# 2_Microcontroler_48.net
KiCad netlist of a schematic drawn in Altium Designer
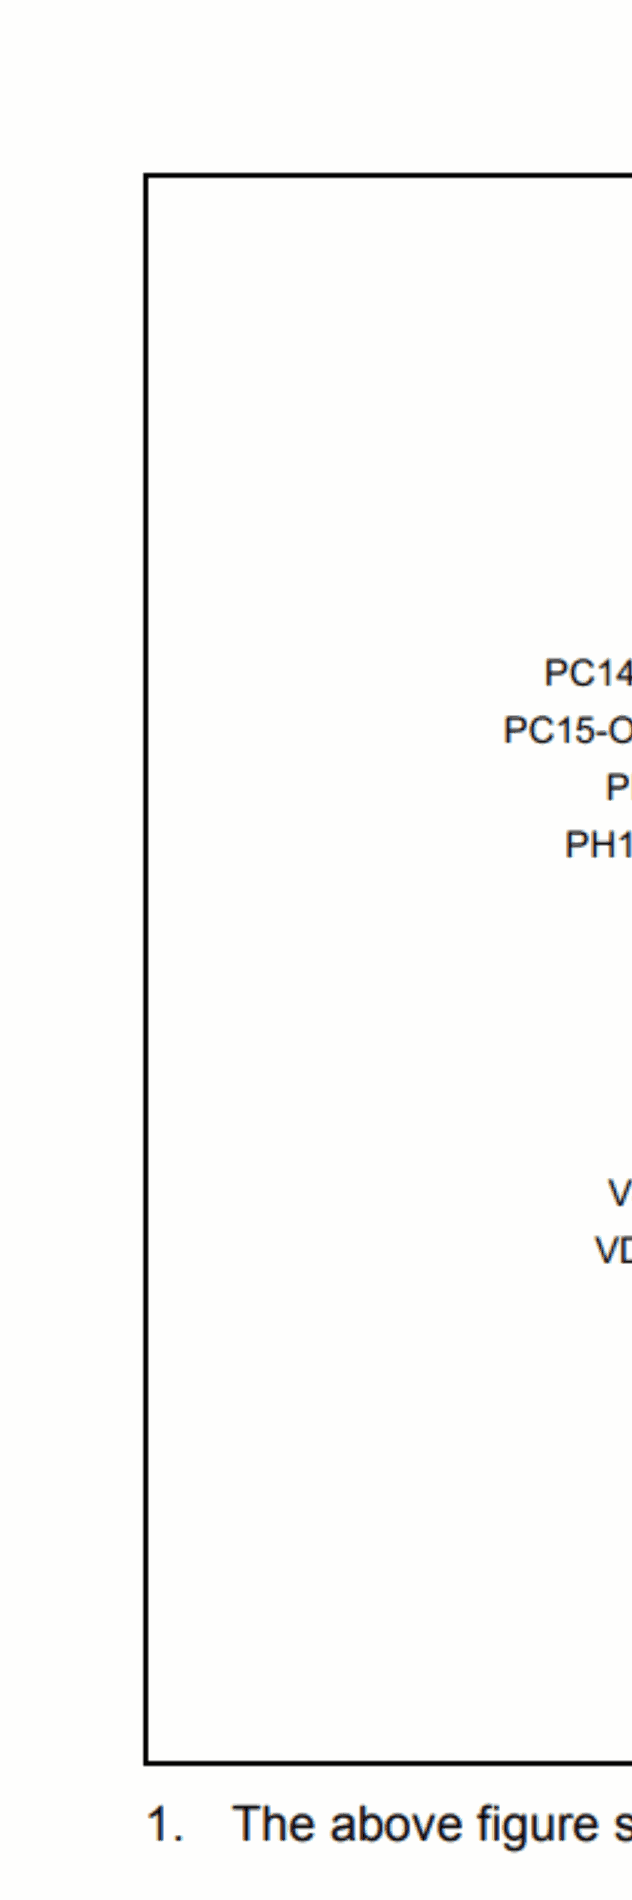
[diagram p0: 2_Microcontroler_48.SchDoc, top left]
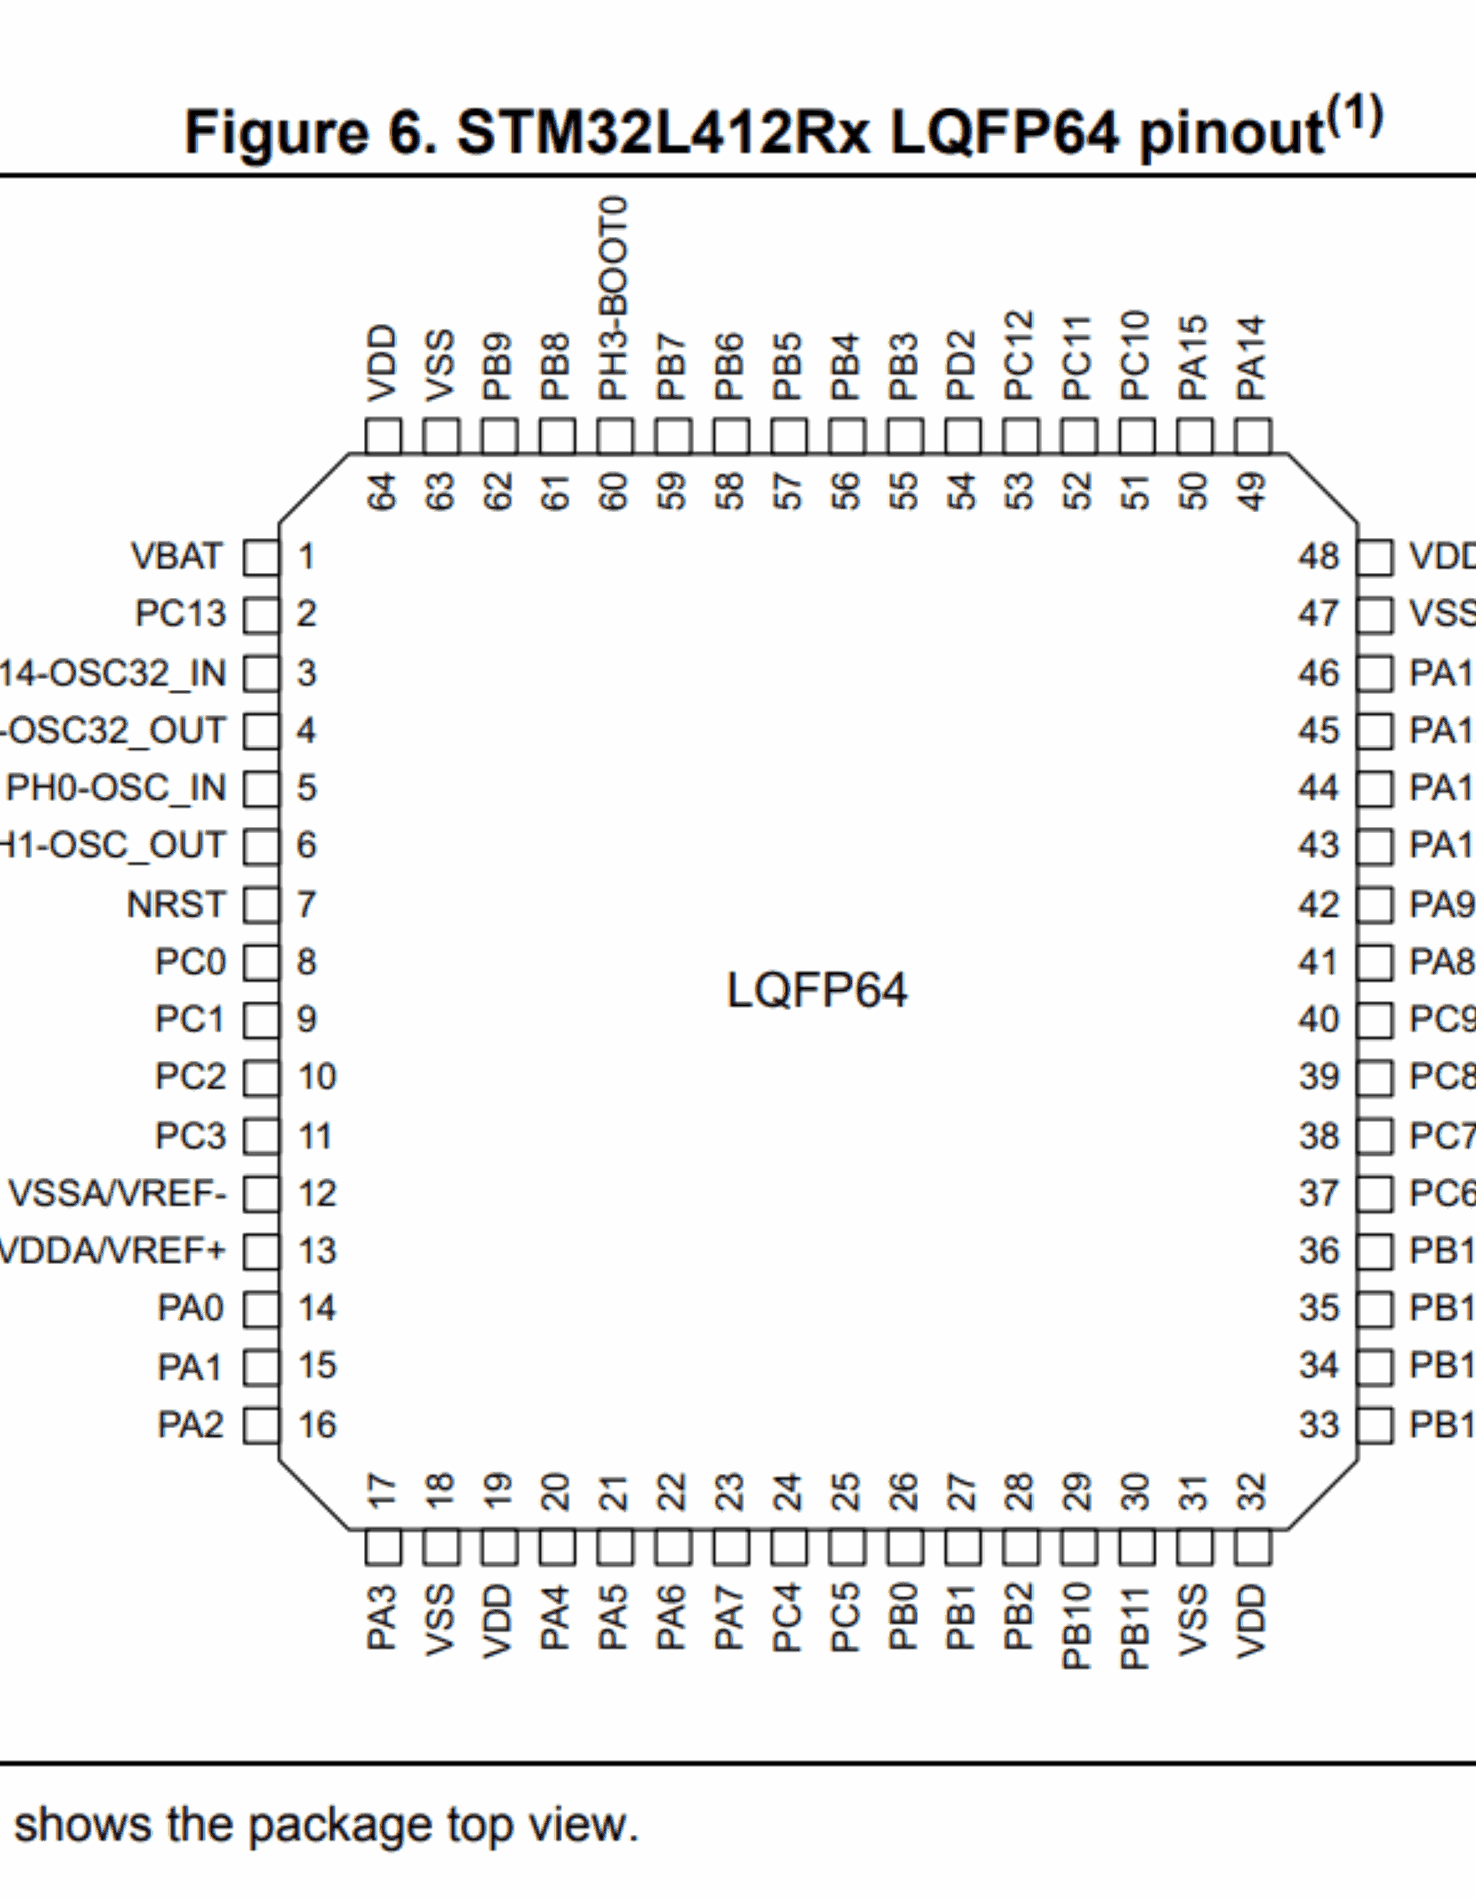
[diagram p1: 2_Microcontroler_48.SchDoc, top middle]
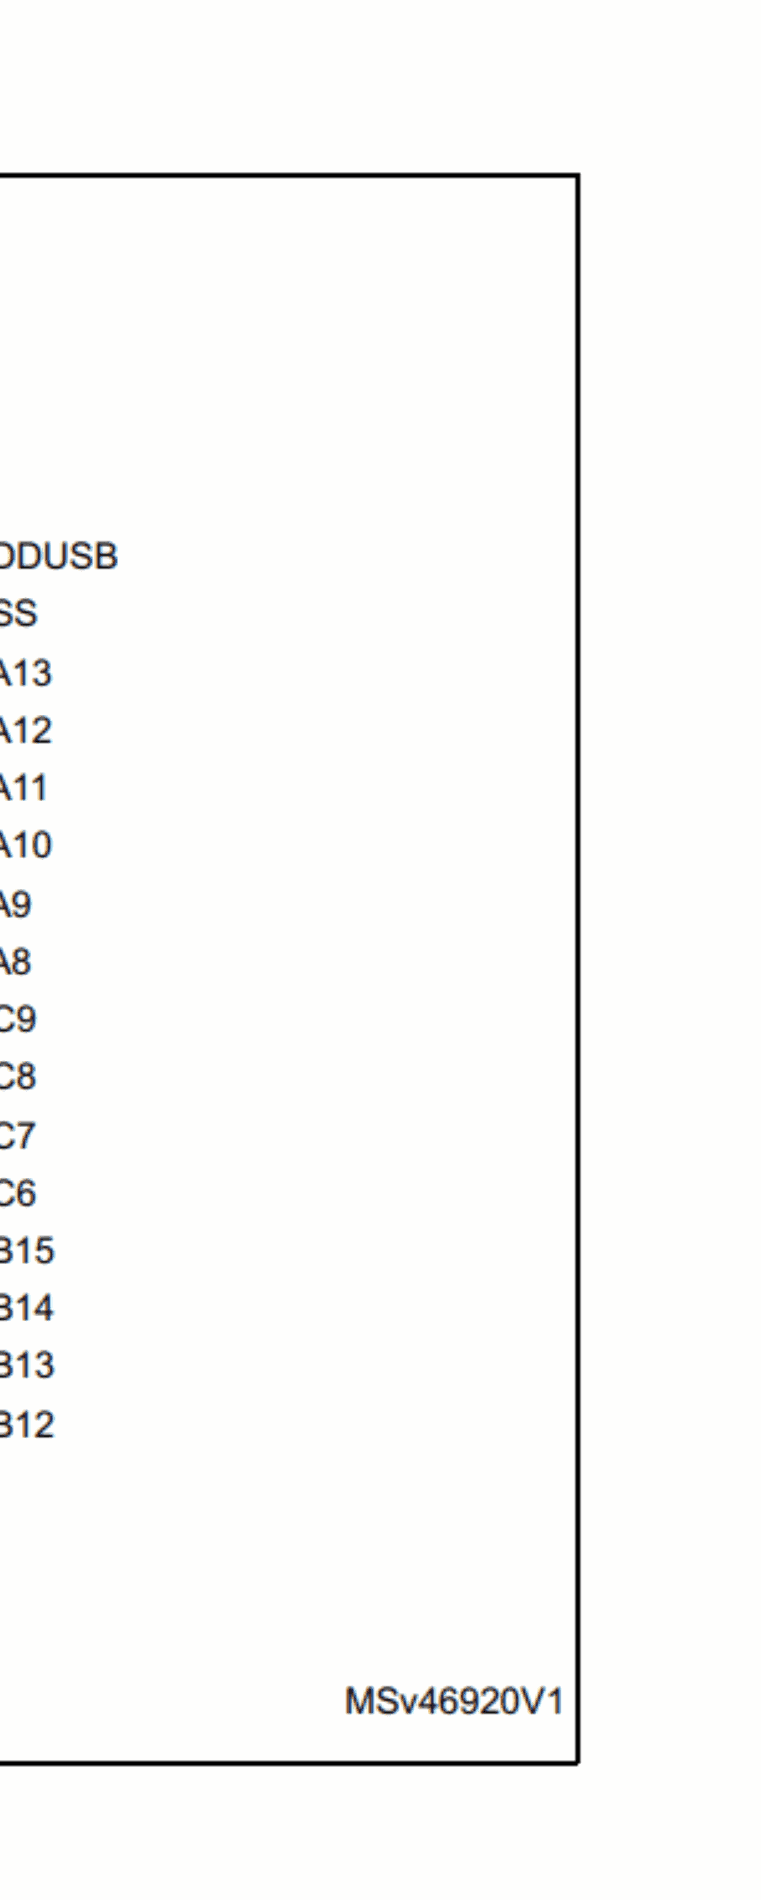
[diagram p2: 2_Microcontroler_48.SchDoc, top right]
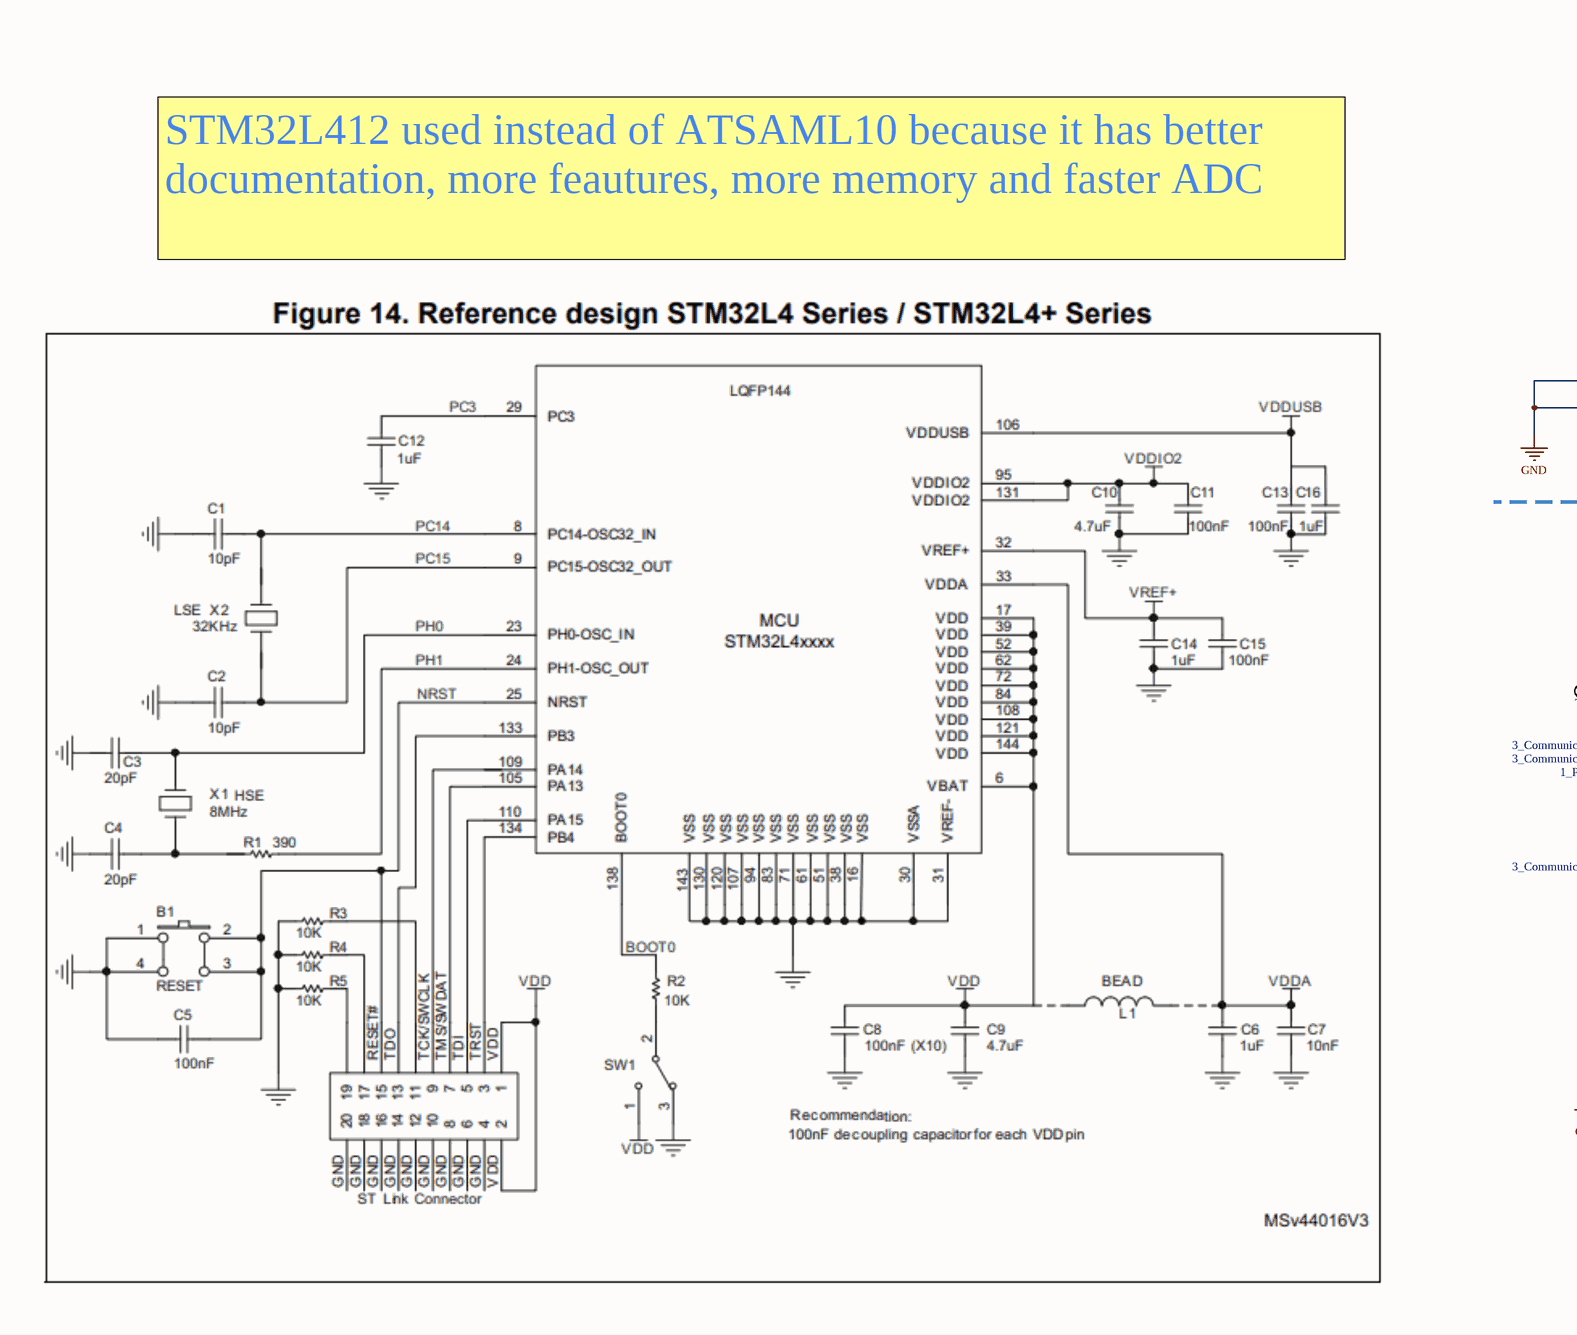
[diagram p3: 2_Microcontroler_48.SchDoc, bottom left]
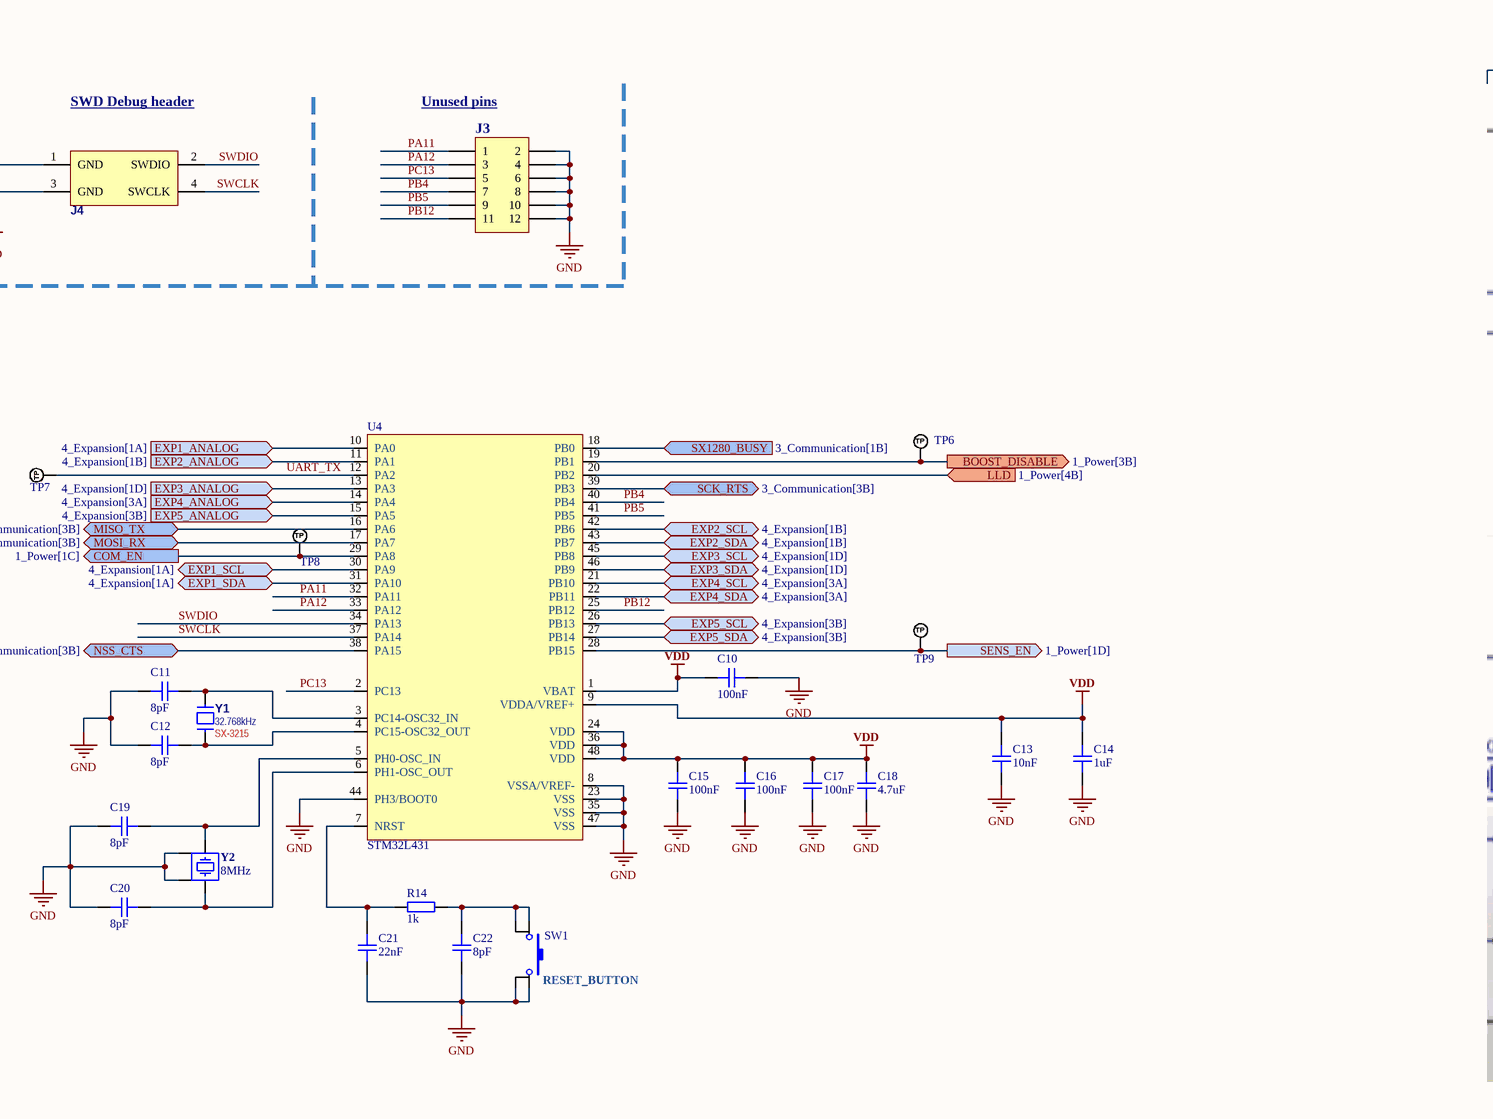
[diagram p4: 2_Microcontroler_48.SchDoc, bottom middle]
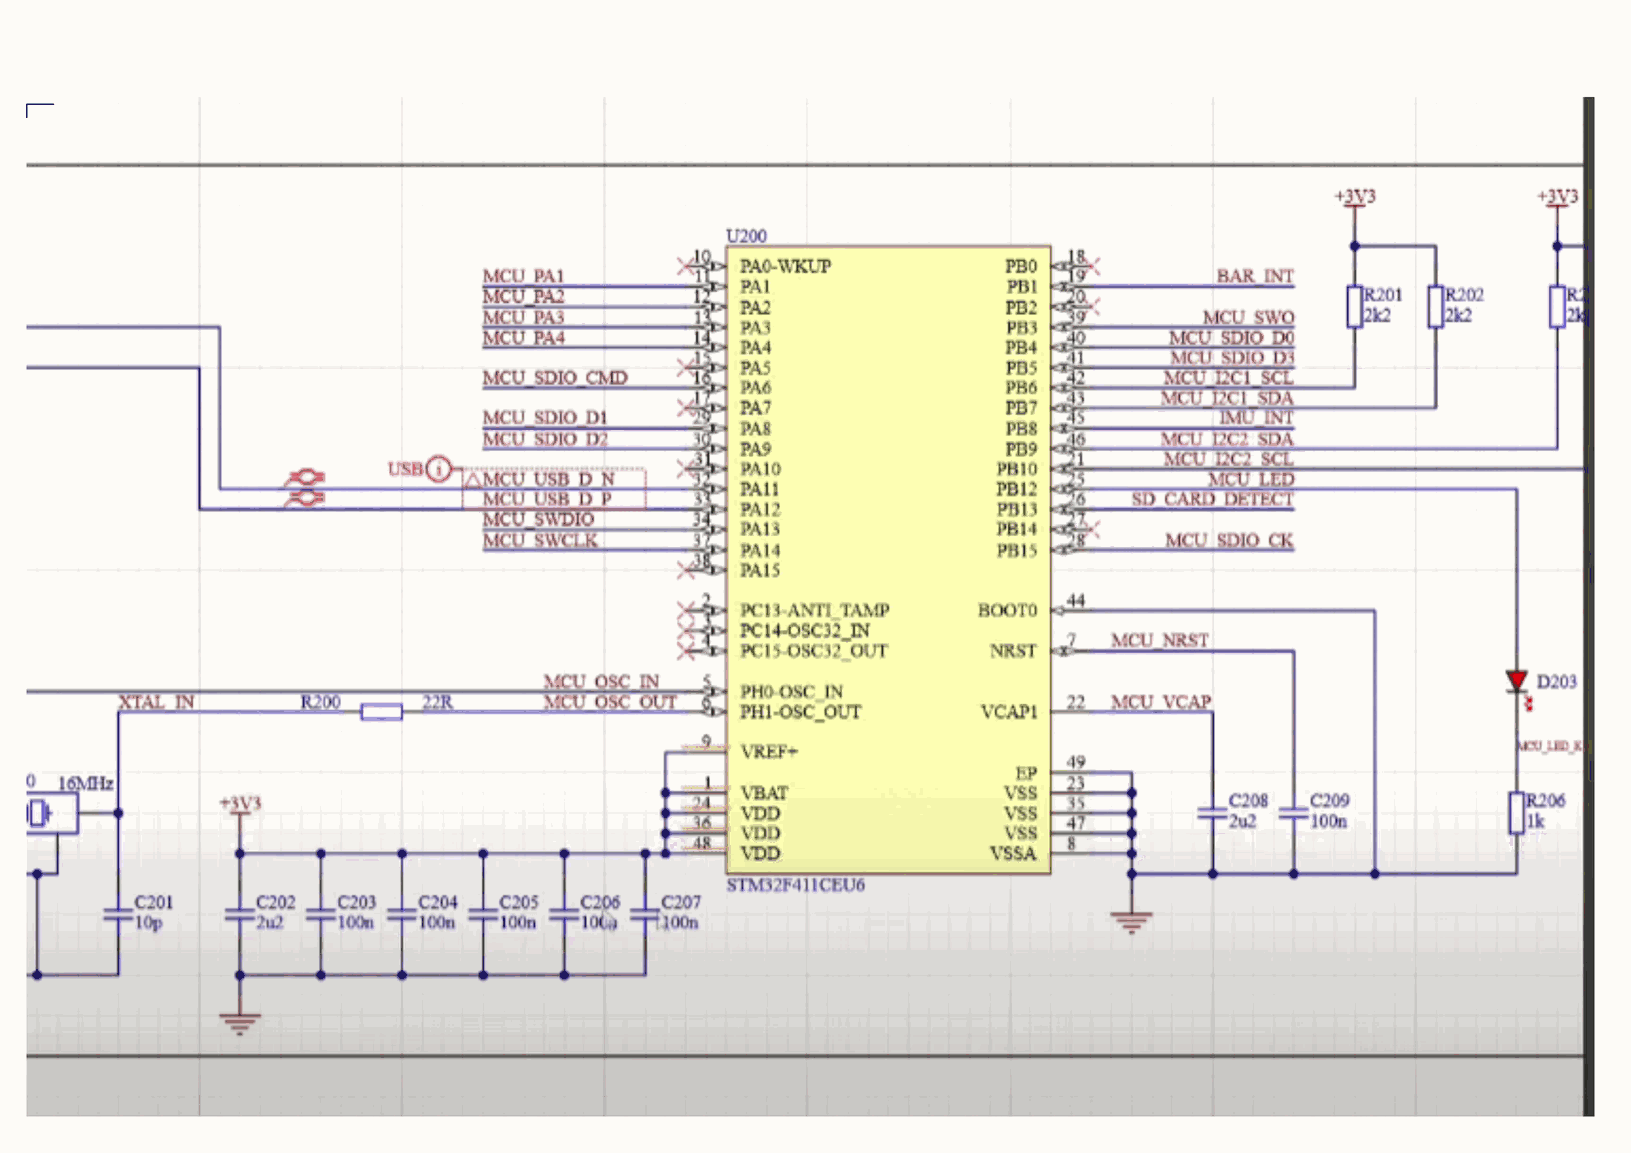
[diagram p5: 2_Microcontroler_48.SchDoc, bottom right]

(export (version "E")
  (design (tool "Eeschema 10.0.6"))
  (components
    (comp (ref "C10")
      (value "100nF")
      (footprint "C0603")
      (description "Capacitor SMD 0603")
      (libsource (lib "Schlib_H2") (part "CAP_0603"))
    )
    (comp (ref "C11")
      (value "8pF")
      (footprint "C0603")
      (description "Capacitor SMD 0603")
      (libsource (lib "Schlib_H2") (part "CAP_0603"))
    )
    (comp (ref "C12")
      (value "8pF")
      (footprint "C0603")
      (description "Capacitor SMD 0603")
      (libsource (lib "Schlib_H2") (part "CAP_0603"))
    )
    (comp (ref "C13")
      (value "10nF")
      (footprint "C0603")
      (description "Capacitor SMD 0603")
      (libsource (lib "Schlib_H2") (part "CAP_0603"))
    )
    (comp (ref "C14")
      (value "1uF")
      (footprint "C0603")
      (description "Capacitor SMD 0603")
      (libsource (lib "Schlib_H2") (part "CAP_0603"))
    )
    (comp (ref "C15")
      (value "100nF")
      (footprint "C0603")
      (description "Capacitor SMD 0603")
      (libsource (lib "Schlib_H2") (part "CAP_0603"))
    )
    (comp (ref "C16")
      (value "100nF")
      (footprint "C0603")
      (description "Capacitor SMD 0603")
      (libsource (lib "Schlib_H2") (part "CAP_0603"))
    )
    (comp (ref "C17")
      (value "100nF")
      (footprint "C0603")
      (description "Capacitor SMD 0603")
      (libsource (lib "Schlib_H2") (part "CAP_0603"))
    )
    (comp (ref "C18")
      (value "4.7uF")
      (footprint "C0603")
      (description "Capacitor SMD 0603")
      (libsource (lib "Schlib_H2") (part "CAP_0603"))
    )
    (comp (ref "C19")
      (value "8pF")
      (footprint "C0603")
      (description "Capacitor SMD 0603")
      (libsource (lib "Schlib_H2") (part "CAP_0603"))
    )
    (comp (ref "C20")
      (value "8pF")
      (footprint "C0603")
      (description "Capacitor SMD 0603")
      (libsource (lib "Schlib_H2") (part "CAP_0603"))
    )
    (comp (ref "C21")
      (value "22nF")
      (footprint "C0603")
      (description "Capacitor SMD 0603")
      (libsource (lib "Schlib_H2") (part "CAP_0603"))
    )
    (comp (ref "C22")
      (value "8pF")
      (footprint "C0603")
      (description "Capacitor SMD 0603")
      (libsource (lib "Schlib_H2") (part "CAP_0603"))
    )
    (comp (ref "J3")
      (value "Header 6X2")
      (footprint "HEADER_6x2_2.54")
      (description "Header, 12-Pin, Dual row")
      (fields (field (name "PUBLISHER") "Altium Limited"))
      (libsource (lib "Schlib_H2") (part "Header 6x2"))
    )
    (comp (ref "J4")
      (value "SWD connector")
      (footprint "HEADER_2x2_2.54")
      (description "Single Wire Debug connector with UART _TX pin")
      (libsource (lib "Schlib_H2") (part "SWD connector"))
    )
    (comp (ref "R14")
      (value "1k")
      (footprint "R0603")
      (description "Resistor SMD 0603")
      (libsource (lib "Schlib_H2") (part "RES_0603"))
    )
    (comp (ref "SW1")
      (value "PTS645SM43SMTR92 LFS")
      (footprint "SW_SKRPACE010")
      (description "Switch")
      (fields (field (name "PUBLISHER") "Altium Limited"))
      (libsource (lib "Schlib_H2") (part "SW-PB"))
    )
    (comp (ref "TP6")
      (value "TP_NOBOM")
      (footprint "TEST_PAD_THD")
      (description "Test Point Round 1mm (NO BOM)")
      (libsource (lib "Schlib_H2") (part "TEST_POINT_RND_1MM"))
    )
    (comp (ref "TP7")
      (value "TP_NOBOM")
      (footprint "TEST_PAD_THD")
      (description "Test Point Round 1mm (NO BOM)")
      (libsource (lib "Schlib_H2") (part "TEST_POINT_RND_1MM"))
    )
    (comp (ref "TP8")
      (value "TP_NOBOM")
      (footprint "TEST_PAD_THD")
      (description "Test Point Round 1mm (NO BOM)")
      (libsource (lib "Schlib_H2") (part "TEST_POINT_RND_1MM"))
    )
    (comp (ref "TP9")
      (value "TP_NOBOM")
      (footprint "TEST_PAD_THD")
      (description "Test Point Round 1mm (NO BOM)")
      (libsource (lib "Schlib_H2") (part "TEST_POINT_RND_1MM"))
    )
    (comp (ref "U4")
      (value "STM32L431")
      (footprint "QFPN-48")
      (description "Ultra-low-power Arm® Cortex®-M4 32-bit MCU+FPU, 100DMIPS,\r\n up to 128KB flash, 40KB SRAM(LQFP48)")
      (libsource (lib "Schlib_H2") (part "STM32L431"))
    )
    (comp (ref "Y1")
      (value "32.768kHz")
      (footprint "CRYSTAL_SX-3215")
      (description "Crystal")
      (fields (field (name "PACKAGEREFERENCE") "SX-3215"))
      (libsource (lib "Schlib_H2") (part "CRYSTAL_1"))
    )
    (comp (ref "Y2")
      (value "8MHz")
      (footprint "CRYSTAL_ECX-32_3.2x2.5x0.8 - duplicate")
      (description "Crystal")
      (fields
        (field (name "MANUFACTURER") "Epson")
        (field (name "MANUFACTURER PART NUMBER") "TSX-3225 24.0000MF15X-AC")
      )
      (libsource (lib "Schlib_H2") (part "Crystal"))
    )
  )
  (nets
    (net (code "1") (name "/BOOST_DISABLE") (class "Default")
      (node (ref "TP6") (pin "1") (pinfunction "TP_1") (pintype "passive"))
      (node (ref "U4") (pin "19") (pinfunction "PB1_19") (pintype "passive"))
    )
    (net (code "2") (name "/COM_EN") (class "Default")
      (node (ref "TP8") (pin "1") (pinfunction "TP_1") (pintype "passive"))
      (node (ref "U4") (pin "29") (pinfunction "PA8_29") (pintype "passive"))
    )
    (net (code "3") (name "/EXP1_ANALOG") (class "Default")
      (node (ref "U4") (pin "10") (pinfunction "PA0_10") (pintype "passive"))
    )
    (net (code "4") (name "/EXP1_SCL") (class "Default")
      (node (ref "U4") (pin "30") (pinfunction "PA9_30") (pintype "passive"))
    )
    (net (code "5") (name "/EXP1_SDA") (class "Default")
      (node (ref "U4") (pin "31") (pinfunction "PA10_31") (pintype "passive"))
    )
    (net (code "6") (name "/EXP2_ANALOG") (class "Default")
      (node (ref "U4") (pin "11") (pinfunction "PA1_11") (pintype "passive"))
    )
    (net (code "7") (name "/EXP2_SCL") (class "Default")
      (node (ref "U4") (pin "42") (pinfunction "PB6_42") (pintype "passive"))
    )
    (net (code "8") (name "/EXP2_SDA") (class "Default")
      (node (ref "U4") (pin "43") (pinfunction "PB7_43") (pintype "passive"))
    )
    (net (code "9") (name "/EXP3_ANALOG") (class "Default")
      (node (ref "U4") (pin "13") (pinfunction "PA3_13") (pintype "passive"))
    )
    (net (code "10") (name "/EXP3_SCL") (class "Default")
      (node (ref "U4") (pin "45") (pinfunction "PB8_45") (pintype "passive"))
    )
    (net (code "11") (name "/EXP3_SDA") (class "Default")
      (node (ref "U4") (pin "46") (pinfunction "PB9_46") (pintype "passive"))
    )
    (net (code "12") (name "/EXP4_ANALOG") (class "Default")
      (node (ref "U4") (pin "14") (pinfunction "PA4_14") (pintype "passive"))
    )
    (net (code "13") (name "/EXP4_SCL") (class "Default")
      (node (ref "U4") (pin "21") (pinfunction "PB10_21") (pintype "passive"))
    )
    (net (code "14") (name "/EXP4_SDA") (class "Default")
      (node (ref "U4") (pin "22") (pinfunction "PB11_22") (pintype "passive"))
    )
    (net (code "15") (name "/EXP5_ANALOG") (class "Default")
      (node (ref "U4") (pin "15") (pinfunction "PA5_15") (pintype "passive"))
    )
    (net (code "16") (name "/EXP5_SCL") (class "Default")
      (node (ref "U4") (pin "26") (pinfunction "PB13_26") (pintype "passive"))
    )
    (net (code "17") (name "/EXP5_SDA") (class "Default")
      (node (ref "U4") (pin "27") (pinfunction "PB14_27") (pintype "passive"))
    )
    (net (code "18") (name "/LLD") (class "Default")
      (node (ref "U4") (pin "20") (pinfunction "PB2_20") (pintype "passive"))
    )
    (net (code "19") (name "/MISO_TX") (class "Default")
      (node (ref "U4") (pin "16") (pinfunction "PA6_16") (pintype "passive"))
    )
    (net (code "20") (name "/MOSI_RX") (class "Default")
      (node (ref "U4") (pin "17") (pinfunction "PA7_17") (pintype "passive"))
    )
    (net (code "21") (name "/NSS_CTS") (class "Default")
      (node (ref "U4") (pin "38") (pinfunction "PA15_38") (pintype "passive"))
    )
    (net (code "22") (name "/PA11") (class "Default")
      (node (ref "J3") (pin "1") (pinfunction "1_1") (pintype "passive"))
      (node (ref "U4") (pin "32") (pinfunction "PA11_32") (pintype "passive"))
    )
    (net (code "23") (name "/PA12") (class "Default")
      (node (ref "J3") (pin "3") (pinfunction "3_3") (pintype "passive"))
      (node (ref "U4") (pin "33") (pinfunction "PA12_33") (pintype "passive"))
    )
    (net (code "24") (name "/PB4") (class "Default")
      (node (ref "J3") (pin "7") (pinfunction "7_7") (pintype "passive"))
      (node (ref "U4") (pin "40") (pinfunction "PB4_40") (pintype "passive"))
    )
    (net (code "25") (name "/PB5") (class "Default")
      (node (ref "J3") (pin "9") (pinfunction "9_9") (pintype "passive"))
      (node (ref "U4") (pin "41") (pinfunction "PB5_41") (pintype "passive"))
    )
    (net (code "26") (name "/PB12") (class "Default")
      (node (ref "J3") (pin "11") (pinfunction "11_11") (pintype "passive"))
      (node (ref "U4") (pin "25") (pinfunction "PB12_25") (pintype "passive"))
    )
    (net (code "27") (name "/PC13") (class "Default")
      (node (ref "J3") (pin "5") (pinfunction "5_5") (pintype "passive"))
      (node (ref "U4") (pin "2") (pinfunction "PC13_2") (pintype "passive"))
    )
    (net (code "28") (name "/SCK_RTS") (class "Default")
      (node (ref "U4") (pin "39") (pinfunction "PB3_39") (pintype "passive"))
    )
    (net (code "29") (name "/SENS_EN") (class "Default")
      (node (ref "TP9") (pin "1") (pinfunction "TP_1") (pintype "passive"))
      (node (ref "U4") (pin "28") (pinfunction "PB15_28") (pintype "passive"))
    )
    (net (code "30") (name "/SWCLK") (class "Default")
      (node (ref "J4") (pin "4") (pinfunction "SWCLK_4") (pintype "passive"))
      (node (ref "U4") (pin "37") (pinfunction "PA14_37") (pintype "passive"))
    )
    (net (code "31") (name "/SWDIO") (class "Default")
      (node (ref "J4") (pin "2") (pinfunction "SWDIO_2") (pintype "passive"))
      (node (ref "U4") (pin "34") (pinfunction "PA13_34") (pintype "passive"))
    )
    (net (code "32") (name "/SX1280_BUSY") (class "Default")
      (node (ref "U4") (pin "18") (pinfunction "PB0_18") (pintype "passive"))
    )
    (net (code "33") (name "/UART_TX") (class "Default")
      (node (ref "TP7") (pin "1") (pinfunction "TP_1") (pintype "passive"))
      (node (ref "U4") (pin "12") (pinfunction "PA2_12") (pintype "passive"))
    )
    (net (code "34") (name "GND") (class "Default")
      (node (ref "C10") (pin "1") (pinfunction "1_1") (pintype "passive"))
      (node (ref "C11") (pin "1") (pinfunction "1_1") (pintype "passive"))
      (node (ref "C12") (pin "1") (pinfunction "1_1") (pintype "passive"))
      (node (ref "C13") (pin "1") (pinfunction "1_1") (pintype "passive"))
      (node (ref "C14") (pin "1") (pinfunction "1_1") (pintype "passive"))
      (node (ref "C15") (pin "1") (pinfunction "1_1") (pintype "passive"))
      (node (ref "C16") (pin "1") (pinfunction "1_1") (pintype "passive"))
      (node (ref "C17") (pin "1") (pinfunction "1_1") (pintype "passive"))
      (node (ref "C18") (pin "1") (pinfunction "1_1") (pintype "passive"))
      (node (ref "C19") (pin "1") (pinfunction "1_1") (pintype "passive"))
      (node (ref "C20") (pin "1") (pinfunction "1_1") (pintype "passive"))
      (node (ref "C21") (pin "1") (pinfunction "1_1") (pintype "passive"))
      (node (ref "C22") (pin "1") (pinfunction "1_1") (pintype "passive"))
      (node (ref "J3") (pin "10") (pinfunction "10_10") (pintype "passive"))
      (node (ref "J3") (pin "12") (pinfunction "12_12") (pintype "passive"))
      (node (ref "J3") (pin "2") (pinfunction "2_2") (pintype "passive"))
      (node (ref "J3") (pin "4") (pinfunction "4_4") (pintype "passive"))
      (node (ref "J3") (pin "6") (pinfunction "6_6") (pintype "passive"))
      (node (ref "J3") (pin "8") (pinfunction "8_8") (pintype "passive"))
      (node (ref "J4") (pin "1") (pinfunction "GND_1") (pintype "passive"))
      (node (ref "J4") (pin "3") (pinfunction "GND_3") (pintype "passive"))
      (node (ref "SW1") (pin "3") (pinfunction "3_3") (pintype "passive"))
      (node (ref "SW1") (pin "4") (pinfunction "4_4") (pintype "passive"))
      (node (ref "U4") (pin "23") (pinfunction "VSS_23") (pintype "passive"))
      (node (ref "U4") (pin "35") (pinfunction "VSS_35") (pintype "passive"))
      (node (ref "U4") (pin "44") (pinfunction "PH3/BOOT0_44") (pintype "passive"))
      (node (ref "U4") (pin "47") (pinfunction "VSS_47") (pintype "passive"))
      (node (ref "U4") (pin "8") (pinfunction "VSSA/VREF-_8") (pintype "passive"))
      (node (ref "Y2") (pin "2") (pinfunction "2_2") (pintype "passive"))
      (node (ref "Y2") (pin "4") (pinfunction "4_4") (pintype "passive"))
    )
    (net (code "35") (name "Net-(C22-Pad2)") (class "Default")
      (node (ref "C22") (pin "2") (pinfunction "2_2") (pintype "passive"))
      (node (ref "R14") (pin "2") (pinfunction "2_2") (pintype "passive"))
      (node (ref "SW1") (pin "1") (pinfunction "1_1") (pintype "passive"))
      (node (ref "SW1") (pin "2") (pinfunction "2_2") (pintype "passive"))
    )
    (net (code "36") (name "Net-(U4-NRST)") (class "Default")
      (node (ref "C21") (pin "2") (pinfunction "2_2") (pintype "passive"))
      (node (ref "R14") (pin "1") (pinfunction "1_1") (pintype "passive"))
      (node (ref "U4") (pin "7") (pinfunction "NRST_7") (pintype "passive"))
    )
    (net (code "37") (name "Net-(U4-PC14-OSC32_IN)") (class "Default")
      (node (ref "C11") (pin "2") (pinfunction "2_2") (pintype "passive"))
      (node (ref "U4") (pin "3") (pinfunction "PC14-OSC32_IN_3") (pintype "passive"))
      (node (ref "Y1") (pin "2") (pinfunction "2_2") (pintype "passive"))
    )
    (net (code "38") (name "Net-(U4-PC15-OSC32_OUT)") (class "Default")
      (node (ref "C12") (pin "2") (pinfunction "2_2") (pintype "passive"))
      (node (ref "U4") (pin "4") (pinfunction "PC15-OSC32_OUT_4") (pintype "passive"))
      (node (ref "Y1") (pin "1") (pinfunction "1_1") (pintype "passive"))
    )
    (net (code "39") (name "Net-(U4-PH0-OSC_IN)") (class "Default")
      (node (ref "C19") (pin "2") (pinfunction "2_2") (pintype "passive"))
      (node (ref "U4") (pin "5") (pinfunction "PH0-OSC_IN_5") (pintype "passive"))
      (node (ref "Y2") (pin "3") (pinfunction "3_3") (pintype "passive"))
    )
    (net (code "40") (name "Net-(U4-PH1-OSC_OUT)") (class "Default")
      (node (ref "C20") (pin "2") (pinfunction "2_2") (pintype "passive"))
      (node (ref "U4") (pin "6") (pinfunction "PH1-OSC_OUT_6") (pintype "passive"))
      (node (ref "Y2") (pin "1") (pinfunction "1_1") (pintype "passive"))
    )
    (net (code "41") (name "VDD") (class "Default")
      (node (ref "C10") (pin "2") (pinfunction "2_2") (pintype "passive"))
      (node (ref "C13") (pin "2") (pinfunction "2_2") (pintype "passive"))
      (node (ref "C14") (pin "2") (pinfunction "2_2") (pintype "passive"))
      (node (ref "C15") (pin "2") (pinfunction "2_2") (pintype "passive"))
      (node (ref "C16") (pin "2") (pinfunction "2_2") (pintype "passive"))
      (node (ref "C17") (pin "2") (pinfunction "2_2") (pintype "passive"))
      (node (ref "C18") (pin "2") (pinfunction "2_2") (pintype "passive"))
      (node (ref "U4") (pin "1") (pinfunction "VBAT_1") (pintype "passive"))
      (node (ref "U4") (pin "24") (pinfunction "VDD_24") (pintype "passive"))
      (node (ref "U4") (pin "36") (pinfunction "VDD_36") (pintype "passive"))
      (node (ref "U4") (pin "48") (pinfunction "VDD_48") (pintype "passive"))
      (node (ref "U4") (pin "9") (pinfunction "VDDA/VREF+_9") (pintype "passive"))
    )
  )
)
